# Sheet_Course_Mitr.net
KiCad netlist of a schematic drawn in Altium Designer
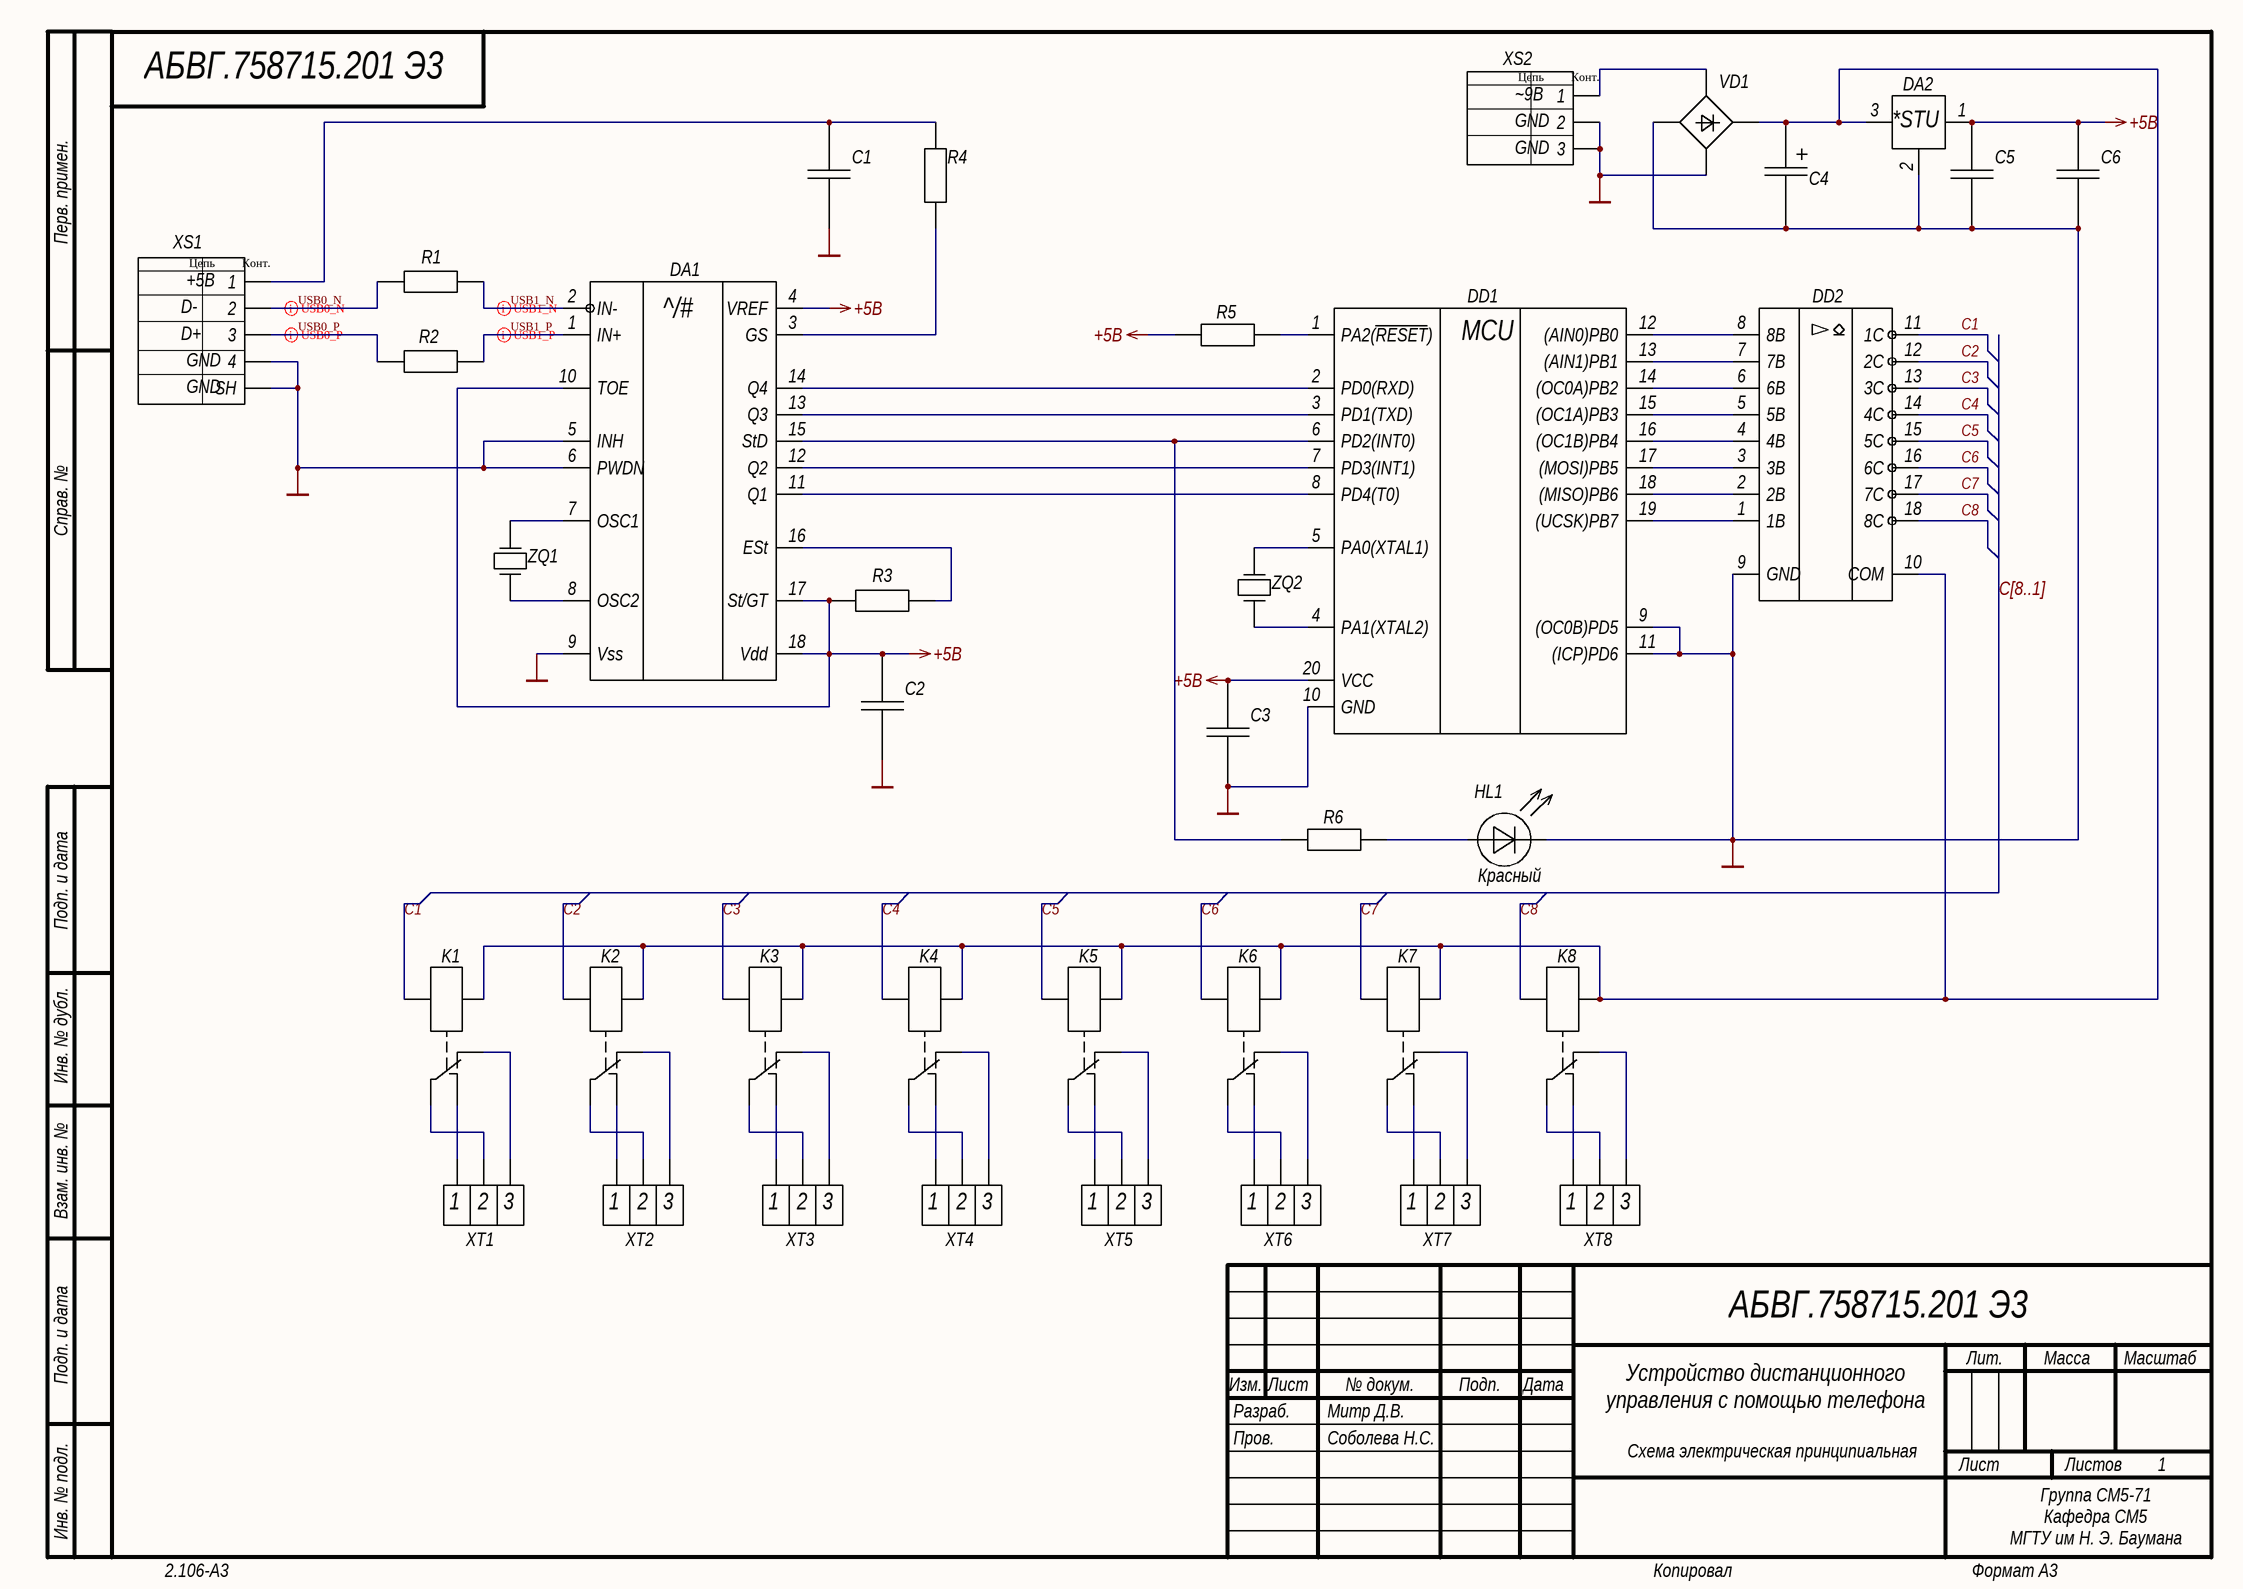
[diagram p0: Sheet_Course_Mitr.SchDoc]

(export (version "E")
  (design (tool "Eeschema 10.0.6"))
  (components
    (comp (ref "C1")
      (value "0,1 мкФ")
      (footprint "0805_CAP")
      (libsource (lib "Schlib_Course_Mitr") (part "Capacitor"))
    )
    (comp (ref "C2")
      (value "0,1 мкФ")
      (footprint "0805_CAP")
      (libsource (lib "Schlib_Course_Mitr") (part "Capacitor"))
    )
    (comp (ref "C3")
      (value "0,1 мкФ")
      (footprint "0805_CAP")
      (libsource (lib "Schlib_Course_Mitr") (part "Capacitor"))
    )
    (comp (ref "C4")
      (value "2200 мкФ")
      (footprint "Pol_CAP")
      (libsource (lib "Schlib_Course_Mitr") (part "Capacitor_pol"))
    )
    (comp (ref "C5")
      (value "0,1 мкФ")
      (footprint "0805_CAP")
      (libsource (lib "Schlib_Course_Mitr") (part "Capacitor"))
    )
    (comp (ref "C6")
      (value "0,1 мкФ")
      (footprint "0805_CAP")
      (libsource (lib "Schlib_Course_Mitr") (part "Capacitor"))
    )
    (comp (ref "DA1")
      (value "MT8870DS")
      (footprint "CM8870C-SOP18")
      (libsource (lib "Schlib_Course_Mitr") (part "MT8870DS"))
    )
    (comp (ref "DA2") (value "78L05") (footprint "STU") (libsource (lib "Schlib_Course_Mitr") (part "STU")))
    (comp (ref "DD1")
      (value "ATtiny2313")
      (footprint "ATtiny2313-SOP20")
      (libsource (lib "Schlib_Course_Mitr") (part "ATtiny2313"))
    )
    (comp (ref "DD2")
      (value "ULN2803A")
      (footprint "ULN2803-SOP18")
      (libsource (lib "Schlib_Course_Mitr") (part "ULN2803A"))
    )
    (comp (ref "HL1")
      (value "Красный")
      (footprint "Blink_RED")
      (fields (field (name "VALUEMANUFACTURERPARTNUMBER") "fyls-0603urc"))
      (libsource (lib "Schlib_Course_Mitr") (part "Led_red"))
    )
    (comp (ref "K1")
      (value "LEG-12")
      (footprint "LEG-12")
      (libsource (lib "Schlib_Course_Mitr") (part "Relay"))
    )
    (comp (ref "K2")
      (value "LEG-12")
      (footprint "LEG-12")
      (libsource (lib "Schlib_Course_Mitr") (part "Relay"))
    )
    (comp (ref "K3")
      (value "LEG-12")
      (footprint "LEG-12")
      (libsource (lib "Schlib_Course_Mitr") (part "Relay"))
    )
    (comp (ref "K4")
      (value "LEG-12")
      (footprint "LEG-12")
      (libsource (lib "Schlib_Course_Mitr") (part "Relay"))
    )
    (comp (ref "K5")
      (value "LEG-12")
      (footprint "LEG-12")
      (libsource (lib "Schlib_Course_Mitr") (part "Relay"))
    )
    (comp (ref "K6")
      (value "LEG-12")
      (footprint "LEG-12")
      (libsource (lib "Schlib_Course_Mitr") (part "Relay"))
    )
    (comp (ref "K7")
      (value "LEG-12")
      (footprint "LEG-12")
      (libsource (lib "Schlib_Course_Mitr") (part "Relay"))
    )
    (comp (ref "K8")
      (value "LEG-12")
      (footprint "LEG-12")
      (libsource (lib "Schlib_Course_Mitr") (part "Relay"))
    )
    (comp (ref "R1")
      (value "100 кОм")
      (footprint "0805_RES")
      (libsource (lib "Schlib_Course_Mitr") (part "Resistor"))
    )
    (comp (ref "R2")
      (value "100 кОм")
      (footprint "0805_RES")
      (libsource (lib "Schlib_Course_Mitr") (part "Resistor"))
    )
    (comp (ref "R3")
      (value "300 кОм")
      (footprint "0805_RES")
      (libsource (lib "Schlib_Course_Mitr") (part "Resistor"))
    )
    (comp (ref "R4")
      (value "100 кОм")
      (footprint "0805_RES")
      (libsource (lib "Schlib_Course_Mitr") (part "Resistor"))
    )
    (comp (ref "R5")
      (value "10 кОм")
      (footprint "0805_RES")
      (libsource (lib "Schlib_Course_Mitr") (part "Resistor"))
    )
    (comp (ref "R6")
      (value "1 кОм")
      (footprint "0805_RES")
      (libsource (lib "Schlib_Course_Mitr") (part "Resistor"))
    )
    (comp (ref "VD1")
      (value "DF04S")
      (footprint "Diode_Bridge")
      (libsource (lib "Schlib_Course_Mitr") (part "Diode_bridge"))
    )
    (comp (ref "XS1")
      (value "USB_TypeB")
      (footprint "USB-B TE Connectivity 292304-1")
      (fields (field (name "VALUEMANUFACTURERPARTNUMBER") "292304-1"))
      (libsource (lib "Schlib_Course_Mitr") (part "USB_TypeB"))
    )
    (comp (ref "XS2")
      (value "DJK-02B")
      (footprint "DJK-02B")
      (libsource (lib "Schlib_Course_Mitr") (part "DJK-02B_PWR_CON"))
    )
    (comp (ref "XT1") (value "KLS2") (footprint "pad") (libsource (lib "Schlib_Course_Mitr") (part "pad")))
    (comp (ref "XT2") (value "KLS2") (footprint "pad") (libsource (lib "Schlib_Course_Mitr") (part "pad")))
    (comp (ref "XT3") (value "KLS2") (footprint "pad") (libsource (lib "Schlib_Course_Mitr") (part "pad")))
    (comp (ref "XT4") (value "KLS2") (footprint "pad") (libsource (lib "Schlib_Course_Mitr") (part "pad")))
    (comp (ref "XT5") (value "KLS2") (footprint "pad") (libsource (lib "Schlib_Course_Mitr") (part "pad")))
    (comp (ref "XT6") (value "KLS2") (footprint "pad") (libsource (lib "Schlib_Course_Mitr") (part "pad")))
    (comp (ref "XT7") (value "KLS2") (footprint "pad") (libsource (lib "Schlib_Course_Mitr") (part "pad")))
    (comp (ref "XT8") (value "KLS2") (footprint "pad") (libsource (lib "Schlib_Course_Mitr") (part "pad")))
    (comp (ref "ZQ1") (value "~") (footprint "Quartz") (libsource (lib "Schlib_Course_Mitr") (part "Quartz")))
    (comp (ref "ZQ2") (value "~") (footprint "Quartz") (libsource (lib "Schlib_Course_Mitr") (part "Quartz")))
  )
  (nets
    (net (code "1") (name "+5В") (class "Default")
      (node (ref "C2") (pin "2") (pinfunction "2_2") (pintype "passive"))
      (node (ref "C3") (pin "2") (pinfunction "2_2") (pintype "passive"))
      (node (ref "C5") (pin "2") (pinfunction "2_2") (pintype "passive"))
      (node (ref "C6") (pin "2") (pinfunction "2_2") (pintype "passive"))
      (node (ref "DA1") (pin "10") (pinfunction "TOE_10") (pintype "passive"))
      (node (ref "DA1") (pin "17") (pinfunction "St/GT_17") (pintype "passive"))
      (node (ref "DA1") (pin "18") (pinfunction "Vdd_18") (pintype "passive"))
      (node (ref "DA1") (pin "4") (pinfunction "VREF_4") (pintype "passive"))
      (node (ref "DA2") (pin "1") (pinfunction "1_1") (pintype "passive"))
      (node (ref "DD1") (pin "20") (pinfunction "VCC_20") (pintype "passive"))
      (node (ref "R3") (pin "1") (pinfunction "1_1") (pintype "passive"))
      (node (ref "R5") (pin "2") (pinfunction "2_2") (pintype "passive"))
    )
    (net (code "2") (name "/C1") (class "Default")
      (node (ref "DD2") (pin "11") (pinfunction "1С_11") (pintype "passive"))
      (node (ref "K1") (pin "5") (pinfunction "5_5") (pintype "passive"))
    )
    (net (code "3") (name "/C2") (class "Default")
      (node (ref "DD2") (pin "12") (pinfunction "2С_12") (pintype "passive"))
      (node (ref "K2") (pin "5") (pinfunction "5_5") (pintype "passive"))
    )
    (net (code "4") (name "/C3") (class "Default")
      (node (ref "DD2") (pin "13") (pinfunction "3С_13") (pintype "passive"))
      (node (ref "K3") (pin "5") (pinfunction "5_5") (pintype "passive"))
    )
    (net (code "5") (name "/C4") (class "Default")
      (node (ref "DD2") (pin "14") (pinfunction "4C_14") (pintype "passive"))
      (node (ref "K4") (pin "5") (pinfunction "5_5") (pintype "passive"))
    )
    (net (code "6") (name "/C5") (class "Default")
      (node (ref "DD2") (pin "15") (pinfunction "5С_15") (pintype "passive"))
      (node (ref "K5") (pin "5") (pinfunction "5_5") (pintype "passive"))
    )
    (net (code "7") (name "/C6") (class "Default")
      (node (ref "DD2") (pin "16") (pinfunction "6С_16") (pintype "passive"))
      (node (ref "K6") (pin "5") (pinfunction "5_5") (pintype "passive"))
    )
    (net (code "8") (name "/C7") (class "Default")
      (node (ref "DD2") (pin "17") (pinfunction "7С_17") (pintype "passive"))
      (node (ref "K7") (pin "5") (pinfunction "5_5") (pintype "passive"))
    )
    (net (code "9") (name "/C8") (class "Default")
      (node (ref "DD2") (pin "18") (pinfunction "8С_18") (pintype "passive"))
      (node (ref "K8") (pin "5") (pinfunction "5_5") (pintype "passive"))
    )
    (net (code "11") (name "/USB0_N") (class "Default")
      (node (ref "R1") (pin "2") (pinfunction "2_2") (pintype "passive"))
      (node (ref "XS1") (pin "2") (pinfunction "2_2") (pintype "passive"))
    )
    (net (code "12") (name "/USB0_P") (class "Default")
      (node (ref "R2") (pin "2") (pinfunction "2_2") (pintype "passive"))
      (node (ref "XS1") (pin "3") (pinfunction "3_3") (pintype "passive"))
    )
    (net (code "13") (name "/USB1_N") (class "Default")
      (node (ref "DA1") (pin "2") (pinfunction "IN-_2") (pintype "passive"))
      (node (ref "R1") (pin "1") (pinfunction "1_1") (pintype "passive"))
    )
    (net (code "14") (name "/USB1_P") (class "Default")
      (node (ref "DA1") (pin "1") (pinfunction "IN+_1") (pintype "passive"))
      (node (ref "R2") (pin "1") (pinfunction "1_1") (pintype "passive"))
    )
    (net (code "15") (name "GND") (class "Default")
      (node (ref "C1") (pin "1") (pinfunction "1_1") (pintype "passive"))
      (node (ref "C2") (pin "1") (pinfunction "1_1") (pintype "passive"))
      (node (ref "C3") (pin "1") (pinfunction "1_1") (pintype "passive"))
      (node (ref "C4") (pin "2") (pinfunction "2_2") (pintype "passive"))
      (node (ref "C5") (pin "1") (pinfunction "1_1") (pintype "passive"))
      (node (ref "C6") (pin "1") (pinfunction "1_1") (pintype "passive"))
      (node (ref "DA1") (pin "5") (pinfunction "INH_5") (pintype "passive"))
      (node (ref "DA1") (pin "6") (pinfunction "PWDN_6") (pintype "passive"))
      (node (ref "DA1") (pin "9") (pinfunction "Vss_9") (pintype "passive"))
      (node (ref "DA2") (pin "2") (pinfunction "2_2") (pintype "passive"))
      (node (ref "DD1") (pin "10") (pinfunction "GND_10") (pintype "passive"))
      (node (ref "DD1") (pin "11") (pinfunction "(ICP)PD6_11") (pintype "passive"))
      (node (ref "DD1") (pin "9") (pinfunction "(OC0B)PD5_9") (pintype "passive"))
      (node (ref "DD2") (pin "9") (pinfunction "GND_9") (pintype "passive"))
      (node (ref "HL1") (pin "K") (pinfunction "10_K") (pintype "passive"))
      (node (ref "VD1") (pin "1") (pinfunction "1_1") (pintype "passive"))
      (node (ref "VD1") (pin "4") (pinfunction "4_4") (pintype "passive"))
      (node (ref "XS1") (pin "0") (pinfunction "SH_0") (pintype "passive"))
      (node (ref "XS1") (pin "4") (pinfunction "4_4") (pintype "passive"))
      (node (ref "XS2") (pin "2") (pinfunction "2_2") (pintype "passive"))
      (node (ref "XS2") (pin "3") (pinfunction "3_3") (pintype "passive"))
    )
    (net (code "16") (name "Net-(C1-Pad2)") (class "Default")
      (node (ref "C1") (pin "2") (pinfunction "2_2") (pintype "passive"))
      (node (ref "R4") (pin "1") (pinfunction "1_1") (pintype "passive"))
      (node (ref "XS1") (pin "1") (pinfunction "1_1") (pintype "passive"))
    )
    (net (code "17") (name "Net-(DA1-ESt)") (class "Default")
      (node (ref "DA1") (pin "16") (pinfunction "ESt_16") (pintype "passive"))
      (node (ref "R3") (pin "2") (pinfunction "2_2") (pintype "passive"))
    )
    (net (code "18") (name "Net-(DA1-GS)") (class "Default")
      (node (ref "DA1") (pin "3") (pinfunction "GS_3") (pintype "passive"))
      (node (ref "R4") (pin "2") (pinfunction "2_2") (pintype "passive"))
    )
    (net (code "19") (name "Net-(DA1-OSC1)") (class "Default")
      (node (ref "DA1") (pin "7") (pinfunction "OSC1_7") (pintype "passive"))
      (node (ref "ZQ1") (pin "2") (pinfunction "2_2") (pintype "passive"))
    )
    (net (code "20") (name "Net-(DA1-OSC2)") (class "Default")
      (node (ref "DA1") (pin "8") (pinfunction "OSC2_8") (pintype "passive"))
      (node (ref "ZQ1") (pin "1") (pinfunction "1_1") (pintype "passive"))
    )
    (net (code "21") (name "Net-(DA1-Q1)") (class "Default")
      (node (ref "DA1") (pin "11") (pinfunction "Q1_11") (pintype "passive"))
      (node (ref "DD1") (pin "8") (pinfunction "PD4(T0)_8") (pintype "passive"))
    )
    (net (code "22") (name "Net-(DA1-Q2)") (class "Default")
      (node (ref "DA1") (pin "12") (pinfunction "Q2_12") (pintype "passive"))
      (node (ref "DD1") (pin "7") (pinfunction "PD3(INT1)_7") (pintype "passive"))
    )
    (net (code "23") (name "Net-(DA1-Q3)") (class "Default")
      (node (ref "DA1") (pin "13") (pinfunction "Q3_13") (pintype "passive"))
      (node (ref "DD1") (pin "3") (pinfunction "PD1(TXD)_3") (pintype "passive"))
    )
    (net (code "24") (name "Net-(DA1-Q4)") (class "Default")
      (node (ref "DA1") (pin "14") (pinfunction "Q4_14") (pintype "passive"))
      (node (ref "DD1") (pin "2") (pinfunction "PD0(RXD)_2") (pintype "passive"))
    )
    (net (code "25") (name "Net-(DA1-StD)") (class "Default")
      (node (ref "DA1") (pin "15") (pinfunction "StD_15") (pintype "passive"))
      (node (ref "DD1") (pin "6") (pinfunction "PD2(INT0)_6") (pintype "passive"))
      (node (ref "R6") (pin "2") (pinfunction "2_2") (pintype "passive"))
    )
    (net (code "26") (name "Net-(DD1-(AIN0)PB0)") (class "Default")
      (node (ref "DD1") (pin "12") (pinfunction "(AIN0)PB0_12") (pintype "passive"))
      (node (ref "DD2") (pin "8") (pinfunction "8В_8") (pintype "passive"))
    )
    (net (code "27") (name "Net-(DD1-(AIN1)PB1)") (class "Default")
      (node (ref "DD1") (pin "13") (pinfunction "(AIN1)PB1_13") (pintype "passive"))
      (node (ref "DD2") (pin "7") (pinfunction "7В_7") (pintype "passive"))
    )
    (net (code "28") (name "Net-(DD1-(MISO)PB6)") (class "Default")
      (node (ref "DD1") (pin "18") (pinfunction "(MISO)PB6_18") (pintype "passive"))
      (node (ref "DD2") (pin "2") (pinfunction "2В_2") (pintype "passive"))
    )
    (net (code "29") (name "Net-(DD1-(MOSI)PB5)") (class "Default")
      (node (ref "DD1") (pin "17") (pinfunction "(MOSI)PB5_17") (pintype "passive"))
      (node (ref "DD2") (pin "3") (pinfunction "3В_3") (pintype "passive"))
    )
    (net (code "30") (name "Net-(DD1-(OC0A)PB2)") (class "Default")
      (node (ref "DD1") (pin "14") (pinfunction "(OC0A)PB2_14") (pintype "passive"))
      (node (ref "DD2") (pin "6") (pinfunction "6В_6") (pintype "passive"))
    )
    (net (code "31") (name "Net-(DD1-(OC1A)PB3)") (class "Default")
      (node (ref "DD1") (pin "15") (pinfunction "(OC1A)PB3_15") (pintype "passive"))
      (node (ref "DD2") (pin "5") (pinfunction "5В_5") (pintype "passive"))
    )
    (net (code "32") (name "Net-(DD1-(OC1B)PB4)") (class "Default")
      (node (ref "DD1") (pin "16") (pinfunction "(OC1B)PB4_16") (pintype "passive"))
      (node (ref "DD2") (pin "4") (pinfunction "4В_4") (pintype "passive"))
    )
    (net (code "33") (name "Net-(DD1-(UCSK)PB7)") (class "Default")
      (node (ref "DD1") (pin "19") (pinfunction "(UCSK)PB7_19") (pintype "passive"))
      (node (ref "DD2") (pin "1") (pinfunction "1В_1") (pintype "passive"))
    )
    (net (code "34") (name "Net-(DD1-PA0(XTAL1))") (class "Default")
      (node (ref "DD1") (pin "5") (pinfunction "PA0(XTAL1)_5") (pintype "passive"))
      (node (ref "ZQ2") (pin "2") (pinfunction "2_2") (pintype "passive"))
    )
    (net (code "35") (name "Net-(DD1-PA1(XTAL2))") (class "Default")
      (node (ref "DD1") (pin "4") (pinfunction "PA1(XTAL2)_4") (pintype "passive"))
      (node (ref "ZQ2") (pin "1") (pinfunction "1_1") (pintype "passive"))
    )
    (net (code "36") (name "Net-(DD1-PA2(~{RESET}))") (class "Default")
      (node (ref "DD1") (pin "1") (pinfunction "PA2(~{RESET})_1") (pintype "passive"))
      (node (ref "R5") (pin "1") (pinfunction "1_1") (pintype "passive"))
    )
    (net (code "37") (name "Net-(DD2-COM)") (class "Default")
      (node (ref "C4") (pin "1") (pinfunction "1_1") (pintype "passive"))
      (node (ref "DA2") (pin "3") (pinfunction "3_3") (pintype "passive"))
      (node (ref "DD2") (pin "10") (pinfunction "COM_10") (pintype "passive"))
      (node (ref "K1") (pin "4") (pinfunction "4_4") (pintype "passive"))
      (node (ref "K2") (pin "4") (pinfunction "4_4") (pintype "passive"))
      (node (ref "K3") (pin "4") (pinfunction "4_4") (pintype "passive"))
      (node (ref "K4") (pin "4") (pinfunction "4_4") (pintype "passive"))
      (node (ref "K5") (pin "4") (pinfunction "4_4") (pintype "passive"))
      (node (ref "K6") (pin "4") (pinfunction "4_4") (pintype "passive"))
      (node (ref "K7") (pin "4") (pinfunction "4_4") (pintype "passive"))
      (node (ref "K8") (pin "4") (pinfunction "4_4") (pintype "passive"))
      (node (ref "VD1") (pin "2") (pinfunction "2_2") (pintype "passive"))
    )
    (net (code "38") (name "Net-(HL1-9)") (class "Default")
      (node (ref "HL1") (pin "A") (pinfunction "9_A") (pintype "passive"))
      (node (ref "R6") (pin "1") (pinfunction "1_1") (pintype "passive"))
    )
    (net (code "39") (name "Net-(K1-Pad1)") (class "Default")
      (node (ref "K1") (pin "1") (pinfunction "1_1") (pintype "passive"))
      (node (ref "XT1") (pin "1") (pinfunction "1_1") (pintype "passive"))
    )
    (net (code "40") (name "Net-(K1-Pad2)") (class "Default")
      (node (ref "K1") (pin "2") (pinfunction "2_2") (pintype "passive"))
      (node (ref "XT1") (pin "2") (pinfunction "2_2") (pintype "passive"))
    )
    (net (code "41") (name "Net-(K1-Pad3)") (class "Default")
      (node (ref "K1") (pin "3") (pinfunction "3_3") (pintype "passive"))
      (node (ref "XT1") (pin "3") (pinfunction "3_3") (pintype "passive"))
    )
    (net (code "42") (name "Net-(K2-Pad1)") (class "Default")
      (node (ref "K2") (pin "1") (pinfunction "1_1") (pintype "passive"))
      (node (ref "XT2") (pin "1") (pinfunction "1_1") (pintype "passive"))
    )
    (net (code "43") (name "Net-(K2-Pad2)") (class "Default")
      (node (ref "K2") (pin "2") (pinfunction "2_2") (pintype "passive"))
      (node (ref "XT2") (pin "2") (pinfunction "2_2") (pintype "passive"))
    )
    (net (code "44") (name "Net-(K2-Pad3)") (class "Default")
      (node (ref "K2") (pin "3") (pinfunction "3_3") (pintype "passive"))
      (node (ref "XT2") (pin "3") (pinfunction "3_3") (pintype "passive"))
    )
    (net (code "45") (name "Net-(K3-Pad1)") (class "Default")
      (node (ref "K3") (pin "1") (pinfunction "1_1") (pintype "passive"))
      (node (ref "XT3") (pin "1") (pinfunction "1_1") (pintype "passive"))
    )
    (net (code "46") (name "Net-(K3-Pad2)") (class "Default")
      (node (ref "K3") (pin "2") (pinfunction "2_2") (pintype "passive"))
      (node (ref "XT3") (pin "2") (pinfunction "2_2") (pintype "passive"))
    )
    (net (code "47") (name "Net-(K3-Pad3)") (class "Default")
      (node (ref "K3") (pin "3") (pinfunction "3_3") (pintype "passive"))
      (node (ref "XT3") (pin "3") (pinfunction "3_3") (pintype "passive"))
    )
    (net (code "48") (name "Net-(K4-Pad1)") (class "Default")
      (node (ref "K4") (pin "1") (pinfunction "1_1") (pintype "passive"))
      (node (ref "XT4") (pin "1") (pinfunction "1_1") (pintype "passive"))
    )
    (net (code "49") (name "Net-(K4-Pad2)") (class "Default")
      (node (ref "K4") (pin "2") (pinfunction "2_2") (pintype "passive"))
      (node (ref "XT4") (pin "2") (pinfunction "2_2") (pintype "passive"))
    )
    (net (code "50") (name "Net-(K4-Pad3)") (class "Default")
      (node (ref "K4") (pin "3") (pinfunction "3_3") (pintype "passive"))
      (node (ref "XT4") (pin "3") (pinfunction "3_3") (pintype "passive"))
    )
    (net (code "51") (name "Net-(K5-Pad1)") (class "Default")
      (node (ref "K5") (pin "1") (pinfunction "1_1") (pintype "passive"))
      (node (ref "XT5") (pin "1") (pinfunction "1_1") (pintype "passive"))
    )
    (net (code "52") (name "Net-(K5-Pad2)") (class "Default")
      (node (ref "K5") (pin "2") (pinfunction "2_2") (pintype "passive"))
      (node (ref "XT5") (pin "2") (pinfunction "2_2") (pintype "passive"))
    )
    (net (code "53") (name "Net-(K5-Pad3)") (class "Default")
      (node (ref "K5") (pin "3") (pinfunction "3_3") (pintype "passive"))
      (node (ref "XT5") (pin "3") (pinfunction "3_3") (pintype "passive"))
    )
    (net (code "54") (name "Net-(K6-Pad1)") (class "Default")
      (node (ref "K6") (pin "1") (pinfunction "1_1") (pintype "passive"))
      (node (ref "XT6") (pin "1") (pinfunction "1_1") (pintype "passive"))
    )
    (net (code "55") (name "Net-(K6-Pad2)") (class "Default")
      (node (ref "K6") (pin "2") (pinfunction "2_2") (pintype "passive"))
      (node (ref "XT6") (pin "2") (pinfunction "2_2") (pintype "passive"))
    )
    (net (code "56") (name "Net-(K6-Pad3)") (class "Default")
      (node (ref "K6") (pin "3") (pinfunction "3_3") (pintype "passive"))
      (node (ref "XT6") (pin "3") (pinfunction "3_3") (pintype "passive"))
    )
    (net (code "57") (name "Net-(K7-Pad1)") (class "Default")
      (node (ref "K7") (pin "1") (pinfunction "1_1") (pintype "passive"))
      (node (ref "XT7") (pin "1") (pinfunction "1_1") (pintype "passive"))
    )
    (net (code "58") (name "Net-(K7-Pad2)") (class "Default")
      (node (ref "K7") (pin "2") (pinfunction "2_2") (pintype "passive"))
      (node (ref "XT7") (pin "2") (pinfunction "2_2") (pintype "passive"))
    )
    (net (code "59") (name "Net-(K7-Pad3)") (class "Default")
      (node (ref "K7") (pin "3") (pinfunction "3_3") (pintype "passive"))
      (node (ref "XT7") (pin "3") (pinfunction "3_3") (pintype "passive"))
    )
    (net (code "60") (name "Net-(K8-Pad1)") (class "Default")
      (node (ref "K8") (pin "1") (pinfunction "1_1") (pintype "passive"))
      (node (ref "XT8") (pin "1") (pinfunction "1_1") (pintype "passive"))
    )
    (net (code "61") (name "Net-(K8-Pad2)") (class "Default")
      (node (ref "K8") (pin "2") (pinfunction "2_2") (pintype "passive"))
      (node (ref "XT8") (pin "2") (pinfunction "2_2") (pintype "passive"))
    )
    (net (code "62") (name "Net-(K8-Pad3)") (class "Default")
      (node (ref "K8") (pin "3") (pinfunction "3_3") (pintype "passive"))
      (node (ref "XT8") (pin "3") (pinfunction "3_3") (pintype "passive"))
    )
    (net (code "63") (name "Net-(VD1-Pad3)") (class "Default")
      (node (ref "VD1") (pin "3") (pinfunction "3_3") (pintype "passive"))
      (node (ref "XS2") (pin "1") (pinfunction "1_1") (pintype "passive"))
    )
  )
)
